# Power.net
KiCad netlist of a schematic drawn in Altium Designer
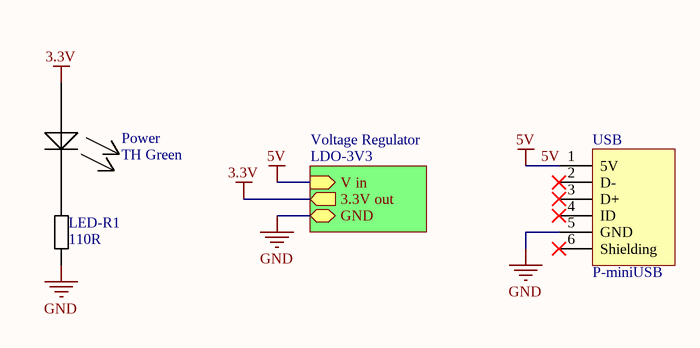
[diagram p0: Power.SchDoc]

(export (version "E")
  (design (tool "Eeschema 10.0.6"))
  (components
    (comp (ref "LED-R1")
      (value "110R")
      (footprint "R 0805 / 2012")
      (libsource (lib "Standard") (part "Resistor"))
    )
    (comp (ref "Power") (value "TH Green") (footprint "LED 3mm") (libsource (lib "LEDs") (part "LED")))
    (comp (ref "USB")
      (value "P-miniUSB")
      (footprint "miniUSB")
      (libsource (lib "Connectors") (part "miniUSB"))
    )
  )
  (nets
    (net (code "1") (name "3.3V") (class "Default")
      (node (ref "Power") (pin "1") (pinfunction "+_1") (pintype "passive"))
    )
    (net (code "2") (name "5V") (class "Default")
      (node (ref "USB") (pin "1") (pinfunction "5V_1") (pintype "passive"))
    )
    (net (code "3") (name "GND") (class "Default")
      (node (ref "LED-R1") (pin "1") (pinfunction "1_1") (pintype "passive"))
      (node (ref "USB") (pin "5") (pinfunction "GND_5") (pintype "passive"))
    )
    (net (code "4") (name "Net-(Power--)") (class "Default")
      (node (ref "LED-R1") (pin "2") (pinfunction "2_2") (pintype "passive"))
      (node (ref "Power") (pin "2") (pinfunction "-_2") (pintype "passive"))
    )
    (net (code "5") (name "unconnected-(USB-D+-Pad3)") (class "Default")
      (node (ref "USB") (pin "3") (pinfunction "D+_3") (pintype "passive+no_connect"))
    )
    (net (code "6") (name "unconnected-(USB-D--Pad2)") (class "Default")
      (node (ref "USB") (pin "2") (pinfunction "D-_2") (pintype "passive+no_connect"))
    )
    (net (code "7") (name "unconnected-(USB-ID-Pad4)") (class "Default")
      (node (ref "USB") (pin "4") (pinfunction "ID_4") (pintype "passive+no_connect"))
    )
    (net (code "8") (name "unconnected-(USB-Shielding-Pad6)") (class "Default")
      (node (ref "USB") (pin "6") (pinfunction "Shielding_6") (pintype "passive+no_connect"))
    )
  )
)
